# primary.net
KiCad netlist of a schematic drawn in EAGLE
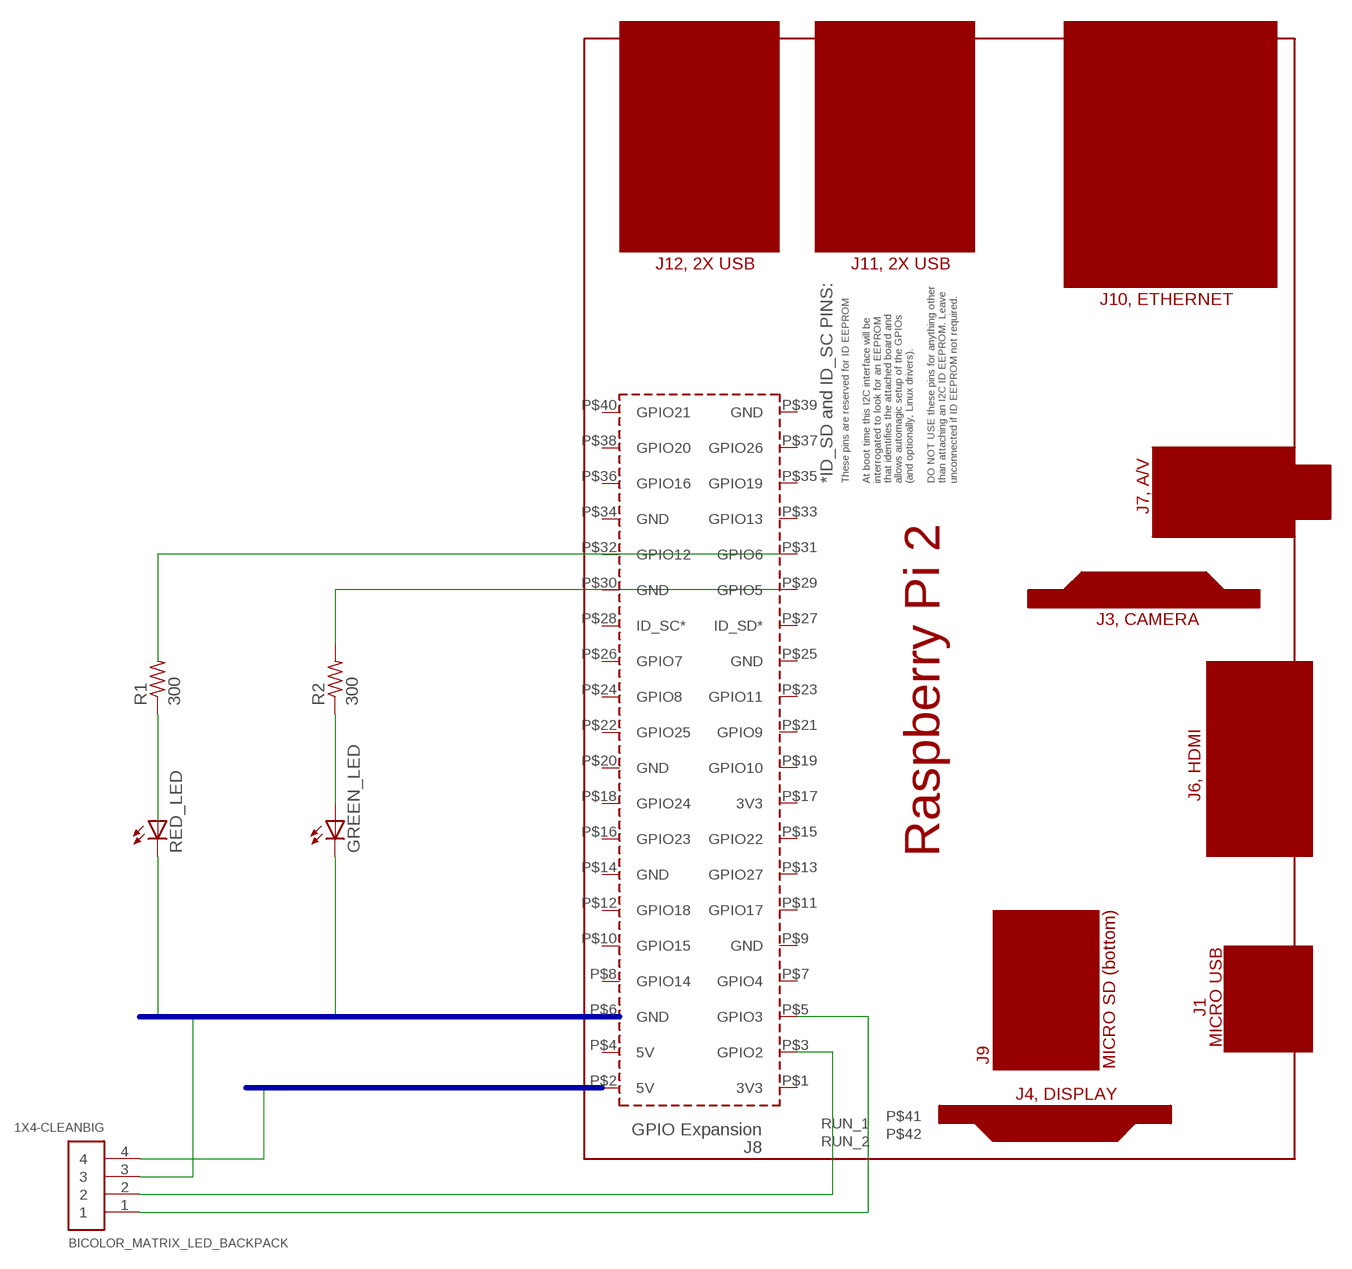
[diagram p0: schematic, sheet 1]

(export (version "E")
  (design (tool "Eeschema 10.0.6"))
  (components
    (comp (ref "BICOLOR_MATRIX_LED_BACKPACK")
      (value "1X4-CLEANBIG")
      (footprint "eagle-import:1X04-CLEANBIG")
      (libsource (lib "eagle-import") (part "1X4-CLEANBIG"))
    )
    (comp (ref "GREEN_LED")
      (value "LED")
      (footprint "eagle-import:SMARTLED-TTW")
      (libsource (lib "eagle-import") (part "LED"))
    )
    (comp (ref "PCB1")
      (value "RPI2")
      (footprint "eagle-import:RPI2")
      (libsource (lib "eagle-import") (part "RPI2"))
    )
    (comp (ref "R1")
      (value "300")
      (footprint "eagle-import:0207_7")
      (libsource (lib "eagle-import") (part "R-US_0207/7"))
    )
    (comp (ref "R2")
      (value "300")
      (footprint "eagle-import:0207_7")
      (libsource (lib "eagle-import") (part "R-US_0207/7"))
    )
    (comp (ref "RED_LED")
      (value "LED")
      (footprint "eagle-import:SMARTLED-TTW")
      (libsource (lib "eagle-import") (part "LED"))
    )
  )
  (nets
    (net (code "1") (name "Net-(GREEN_LED-A)") (class "Default")
      (node (ref "GREEN_LED") (pin "A@1") (pinfunction "A_A@1") (pintype "passive"))
      (node (ref "R2") (pin "1") (pinfunction "1_1") (pintype "passive"))
    )
    (net (code "2") (name "Net-(PCB1-GPIO2)") (class "Default")
      (node (ref "BICOLOR_MATRIX_LED_BACKPACK") (pin "2") (pinfunction "2_2") (pintype "bidirectional"))
      (node (ref "PCB1") (pin "P$3") (pinfunction "GPIO2_P$3") (pintype "bidirectional"))
    )
    (net (code "3") (name "Net-(PCB1-GPIO3)") (class "Default")
      (node (ref "BICOLOR_MATRIX_LED_BACKPACK") (pin "1") (pinfunction "1_1") (pintype "bidirectional"))
      (node (ref "PCB1") (pin "P$5") (pinfunction "GPIO3_P$5") (pintype "bidirectional"))
    )
    (net (code "4") (name "unconnected-(BICOLOR_MATRIX_LED_BACKPACK-Pad3)") (class "Default")
      (node (ref "BICOLOR_MATRIX_LED_BACKPACK") (pin "3") (pinfunction "3_3") (pintype "bidirectional"))
    )
    (net (code "5") (name "unconnected-(BICOLOR_MATRIX_LED_BACKPACK-Pad4)") (class "Default")
      (node (ref "BICOLOR_MATRIX_LED_BACKPACK") (pin "4") (pinfunction "4_4") (pintype "bidirectional"))
    )
    (net (code "6") (name "unconnected-(GREEN_LED-C-PadC@1)") (class "Default")
      (node (ref "GREEN_LED") (pin "C@1") (pinfunction "C_C@1") (pintype "passive"))
    )
    (net (code "7") (name "unconnected-(PCB1-3V3-PadP$1)") (class "Default")
      (node (ref "PCB1") (pin "P$1") (pinfunction "3V3_P$1") (pintype "bidirectional"))
    )
    (net (code "8") (name "unconnected-(PCB1-3V3-PadP$17)") (class "Default")
      (node (ref "PCB1") (pin "P$17") (pinfunction "3V3_P$17") (pintype "bidirectional"))
    )
    (net (code "9") (name "unconnected-(PCB1-5V-PadP$2)") (class "Default")
      (node (ref "PCB1") (pin "P$2") (pinfunction "5V_P$2") (pintype "bidirectional"))
    )
    (net (code "10") (name "unconnected-(PCB1-5V-PadP$4)") (class "Default")
      (node (ref "PCB1") (pin "P$4") (pinfunction "5V_P$4") (pintype "bidirectional"))
    )
    (net (code "11") (name "unconnected-(PCB1-GND-PadP$6)") (class "Default")
      (node (ref "PCB1") (pin "P$6") (pinfunction "GND_P$6") (pintype "bidirectional"))
    )
    (net (code "12") (name "unconnected-(PCB1-GND-PadP$9)") (class "Default")
      (node (ref "PCB1") (pin "P$9") (pinfunction "GND_P$9") (pintype "bidirectional"))
    )
    (net (code "13") (name "unconnected-(PCB1-GND-PadP$14)") (class "Default")
      (node (ref "PCB1") (pin "P$14") (pinfunction "GND_P$14") (pintype "bidirectional"))
    )
    (net (code "14") (name "unconnected-(PCB1-GND-PadP$20)") (class "Default")
      (node (ref "PCB1") (pin "P$20") (pinfunction "GND_P$20") (pintype "bidirectional"))
    )
    (net (code "15") (name "unconnected-(PCB1-GND-PadP$25)") (class "Default")
      (node (ref "PCB1") (pin "P$25") (pinfunction "GND_P$25") (pintype "bidirectional"))
    )
    (net (code "16") (name "unconnected-(PCB1-GND-PadP$30)") (class "Default")
      (node (ref "PCB1") (pin "P$30") (pinfunction "GND_P$30") (pintype "bidirectional"))
    )
    (net (code "17") (name "unconnected-(PCB1-GND-PadP$34)") (class "Default")
      (node (ref "PCB1") (pin "P$34") (pinfunction "GND_P$34") (pintype "bidirectional"))
    )
    (net (code "18") (name "unconnected-(PCB1-GND-PadP$39)") (class "Default")
      (node (ref "PCB1") (pin "P$39") (pinfunction "GND_P$39") (pintype "bidirectional"))
    )
    (net (code "19") (name "unconnected-(PCB1-GPIO4-PadP$7)") (class "Default")
      (node (ref "PCB1") (pin "P$7") (pinfunction "GPIO4_P$7") (pintype "bidirectional"))
    )
    (net (code "20") (name "unconnected-(PCB1-GPIO5-PadP$29)") (class "Default")
      (node (ref "PCB1") (pin "P$29") (pinfunction "GPIO5_P$29") (pintype "bidirectional"))
    )
    (net (code "21") (name "unconnected-(PCB1-GPIO6-PadP$31)") (class "Default")
      (node (ref "PCB1") (pin "P$31") (pinfunction "GPIO6_P$31") (pintype "bidirectional"))
    )
    (net (code "22") (name "unconnected-(PCB1-GPIO7-PadP$26)") (class "Default")
      (node (ref "PCB1") (pin "P$26") (pinfunction "GPIO7_P$26") (pintype "bidirectional"))
    )
    (net (code "23") (name "unconnected-(PCB1-GPIO8-PadP$24)") (class "Default")
      (node (ref "PCB1") (pin "P$24") (pinfunction "GPIO8_P$24") (pintype "bidirectional"))
    )
    (net (code "24") (name "unconnected-(PCB1-GPIO9-PadP$21)") (class "Default")
      (node (ref "PCB1") (pin "P$21") (pinfunction "GPIO9_P$21") (pintype "bidirectional"))
    )
    (net (code "25") (name "unconnected-(PCB1-GPIO10-PadP$19)") (class "Default")
      (node (ref "PCB1") (pin "P$19") (pinfunction "GPIO10_P$19") (pintype "bidirectional"))
    )
    (net (code "26") (name "unconnected-(PCB1-GPIO11-PadP$23)") (class "Default")
      (node (ref "PCB1") (pin "P$23") (pinfunction "GPIO11_P$23") (pintype "bidirectional"))
    )
    (net (code "27") (name "unconnected-(PCB1-GPIO12-PadP$32)") (class "Default")
      (node (ref "PCB1") (pin "P$32") (pinfunction "GPIO12_P$32") (pintype "bidirectional"))
    )
    (net (code "28") (name "unconnected-(PCB1-GPIO13-PadP$33)") (class "Default")
      (node (ref "PCB1") (pin "P$33") (pinfunction "GPIO13_P$33") (pintype "bidirectional"))
    )
    (net (code "29") (name "unconnected-(PCB1-GPIO14-PadP$8)") (class "Default")
      (node (ref "PCB1") (pin "P$8") (pinfunction "GPIO14_P$8") (pintype "bidirectional"))
    )
    (net (code "30") (name "unconnected-(PCB1-GPIO15-PadP$10)") (class "Default")
      (node (ref "PCB1") (pin "P$10") (pinfunction "GPIO15_P$10") (pintype "bidirectional"))
    )
    (net (code "31") (name "unconnected-(PCB1-GPIO16-PadP$36)") (class "Default")
      (node (ref "PCB1") (pin "P$36") (pinfunction "GPIO16_P$36") (pintype "bidirectional"))
    )
    (net (code "32") (name "unconnected-(PCB1-GPIO17-PadP$11)") (class "Default")
      (node (ref "PCB1") (pin "P$11") (pinfunction "GPIO17_P$11") (pintype "bidirectional"))
    )
    (net (code "33") (name "unconnected-(PCB1-GPIO18-PadP$12)") (class "Default")
      (node (ref "PCB1") (pin "P$12") (pinfunction "GPIO18_P$12") (pintype "bidirectional"))
    )
    (net (code "34") (name "unconnected-(PCB1-GPIO19-PadP$35)") (class "Default")
      (node (ref "PCB1") (pin "P$35") (pinfunction "GPIO19_P$35") (pintype "bidirectional"))
    )
    (net (code "35") (name "unconnected-(PCB1-GPIO20-PadP$38)") (class "Default")
      (node (ref "PCB1") (pin "P$38") (pinfunction "GPIO20_P$38") (pintype "bidirectional"))
    )
    (net (code "36") (name "unconnected-(PCB1-GPIO21-PadP$40)") (class "Default")
      (node (ref "PCB1") (pin "P$40") (pinfunction "GPIO21_P$40") (pintype "bidirectional"))
    )
    (net (code "37") (name "unconnected-(PCB1-GPIO22-PadP$15)") (class "Default")
      (node (ref "PCB1") (pin "P$15") (pinfunction "GPIO22_P$15") (pintype "bidirectional"))
    )
    (net (code "38") (name "unconnected-(PCB1-GPIO23-PadP$16)") (class "Default")
      (node (ref "PCB1") (pin "P$16") (pinfunction "GPIO23_P$16") (pintype "bidirectional"))
    )
    (net (code "39") (name "unconnected-(PCB1-GPIO24-PadP$18)") (class "Default")
      (node (ref "PCB1") (pin "P$18") (pinfunction "GPIO24_P$18") (pintype "bidirectional"))
    )
    (net (code "40") (name "unconnected-(PCB1-GPIO25-PadP$22)") (class "Default")
      (node (ref "PCB1") (pin "P$22") (pinfunction "GPIO25_P$22") (pintype "bidirectional"))
    )
    (net (code "41") (name "unconnected-(PCB1-GPIO26-PadP$37)") (class "Default")
      (node (ref "PCB1") (pin "P$37") (pinfunction "GPIO26_P$37") (pintype "bidirectional"))
    )
    (net (code "42") (name "unconnected-(PCB1-GPIO27-PadP$13)") (class "Default")
      (node (ref "PCB1") (pin "P$13") (pinfunction "GPIO27_P$13") (pintype "bidirectional"))
    )
    (net (code "43") (name "unconnected-(PCB1-ID_SC*-PadP$28)") (class "Default")
      (node (ref "PCB1") (pin "P$28") (pinfunction "ID_SC*_P$28") (pintype "bidirectional"))
    )
    (net (code "44") (name "unconnected-(PCB1-ID_SD*-PadP$27)") (class "Default")
      (node (ref "PCB1") (pin "P$27") (pinfunction "ID_SD*_P$27") (pintype "bidirectional"))
    )
    (net (code "45") (name "unconnected-(PCB1-RUN_1-PadP$41)") (class "Default")
      (node (ref "PCB1") (pin "P$41") (pinfunction "RUN_1_P$41") (pintype "bidirectional"))
    )
    (net (code "46") (name "unconnected-(PCB1-RUN_2-PadP$42)") (class "Default")
      (node (ref "PCB1") (pin "P$42") (pinfunction "RUN_2_P$42") (pintype "bidirectional"))
    )
    (net (code "47") (name "unconnected-(R1-Pad1)") (class "Default")
      (node (ref "R1") (pin "1") (pinfunction "1_1") (pintype "passive"))
    )
    (net (code "48") (name "unconnected-(R1-Pad2)") (class "Default")
      (node (ref "R1") (pin "2") (pinfunction "2_2") (pintype "passive"))
    )
    (net (code "49") (name "unconnected-(R2-Pad2)") (class "Default")
      (node (ref "R2") (pin "2") (pinfunction "2_2") (pintype "passive"))
    )
    (net (code "50") (name "unconnected-(RED_LED-A-PadA@1)") (class "Default")
      (node (ref "RED_LED") (pin "A@1") (pinfunction "A_A@1") (pintype "passive"))
    )
    (net (code "51") (name "unconnected-(RED_LED-C-PadC@1)") (class "Default")
      (node (ref "RED_LED") (pin "C@1") (pinfunction "C_C@1") (pintype "passive"))
    )
  )
)
